# usbmidi_v2.net
KiCad netlist of a schematic drawn in EAGLE
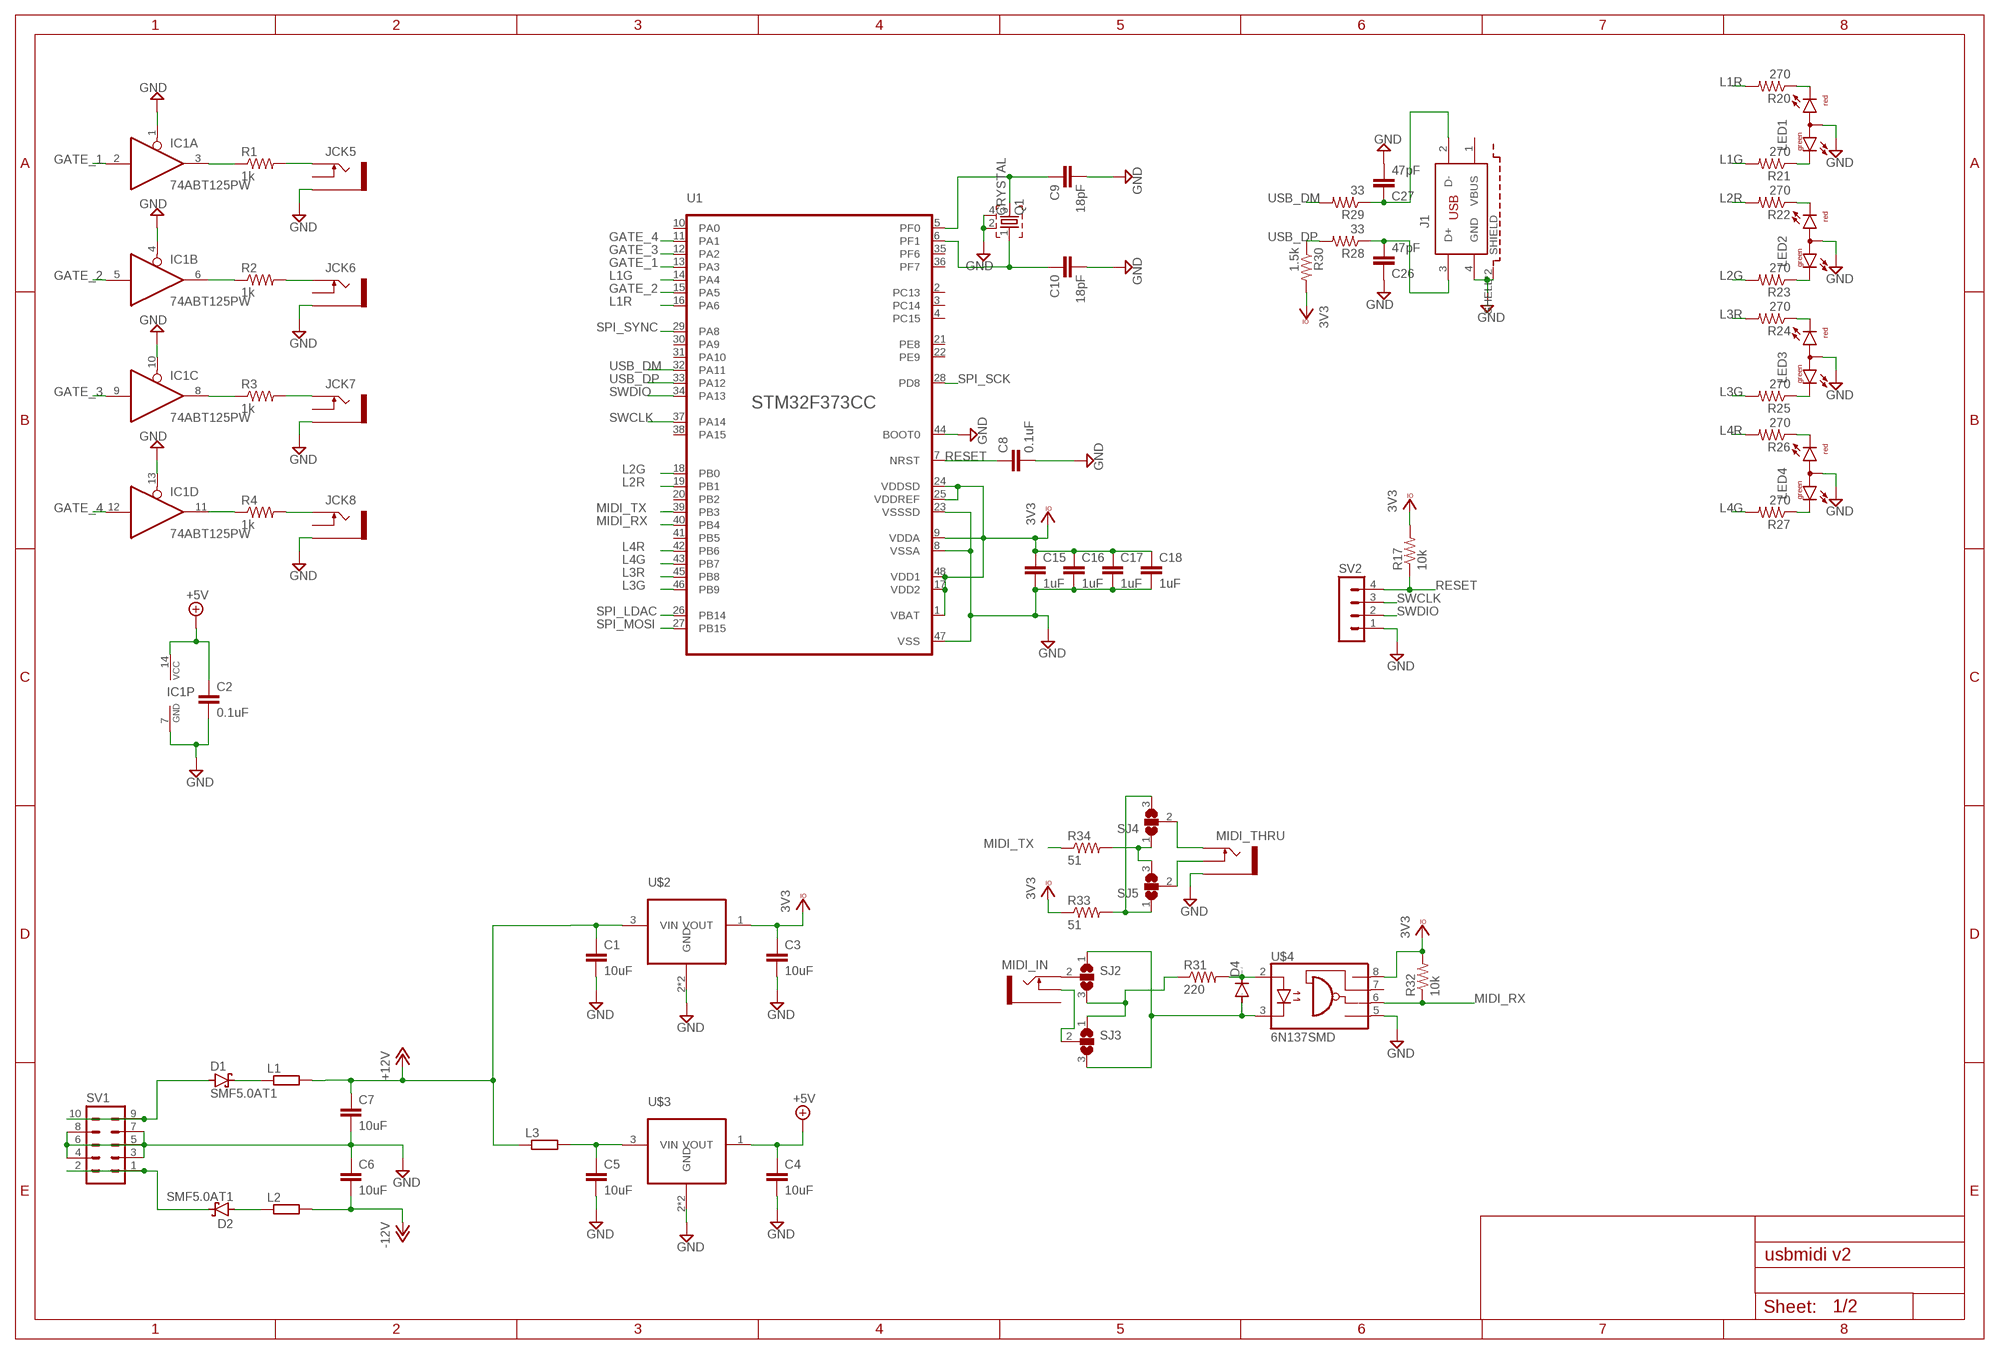
[diagram p0: schematic, sheet 1]
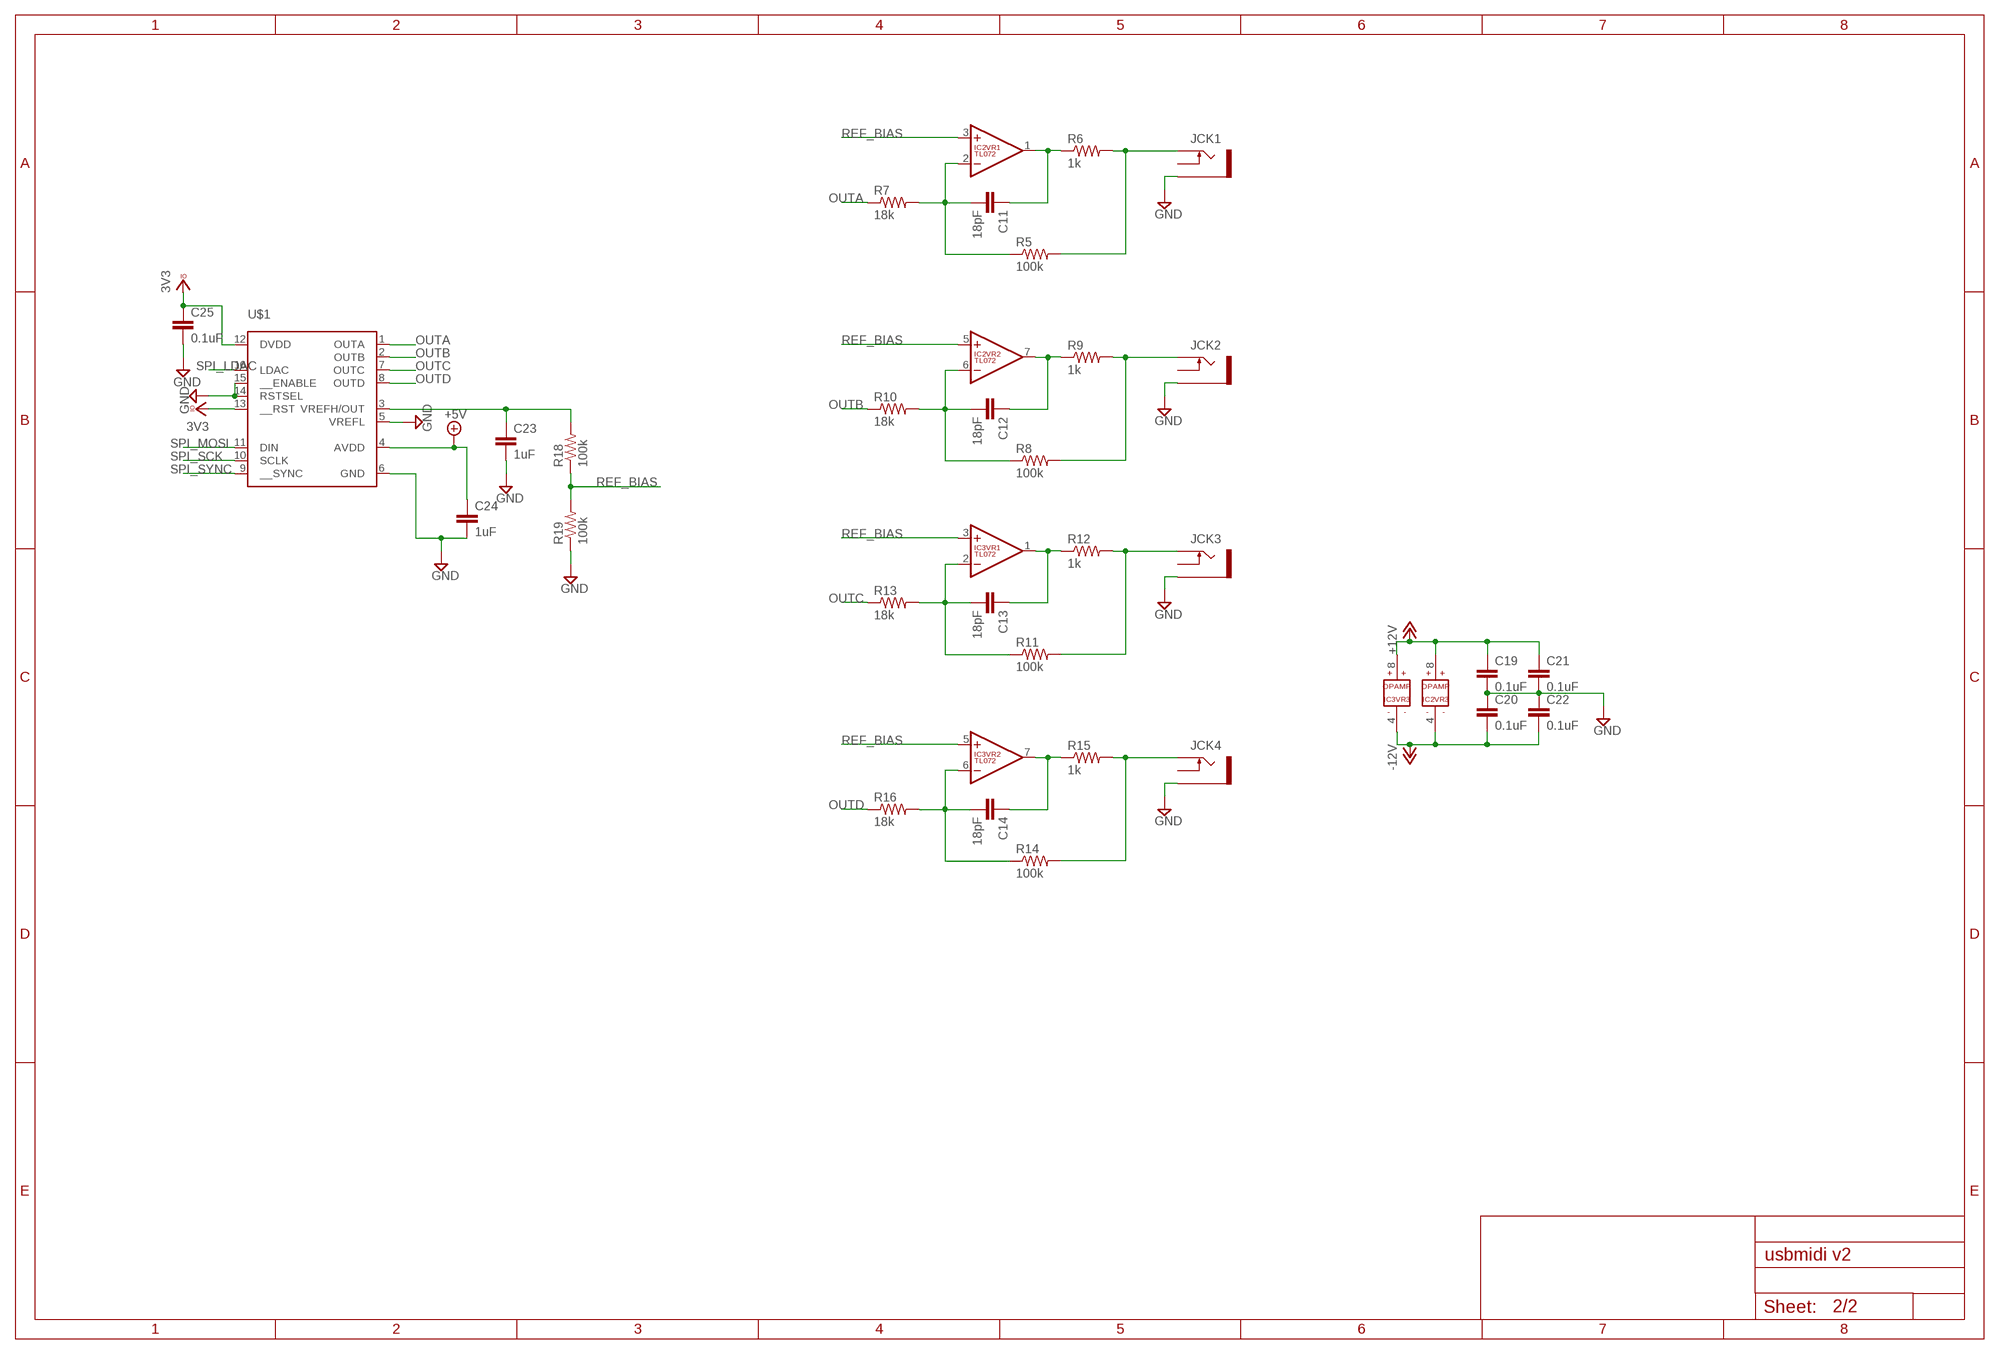
[diagram p1: schematic, sheet 2]

(export (version "E")
  (design (tool "Eeschema 10.0.6"))
  (components
    (comp (ref "C11")
      (value "18pF")
      (footprint "eagle-import:C0603K")
      (libsource (lib "eagle-import") (part "C-EUC0603K"))
    )
    (comp (ref "C12")
      (value "18pF")
      (footprint "eagle-import:C0603K")
      (libsource (lib "eagle-import") (part "C-EUC0603K"))
    )
    (comp (ref "C13")
      (value "18pF")
      (footprint "eagle-import:C0603K")
      (libsource (lib "eagle-import") (part "C-EUC0603K"))
    )
    (comp (ref "C14")
      (value "18pF")
      (footprint "eagle-import:C0603K")
      (libsource (lib "eagle-import") (part "C-EUC0603K"))
    )
    (comp (ref "C19")
      (value "0.1uF")
      (footprint "eagle-import:C0603K")
      (libsource (lib "eagle-import") (part "C-EUC0603K"))
    )
    (comp (ref "C20")
      (value "0.1uF")
      (footprint "eagle-import:C0603K")
      (libsource (lib "eagle-import") (part "C-EUC0603K"))
    )
    (comp (ref "C21")
      (value "0.1uF")
      (footprint "eagle-import:C0603K")
      (libsource (lib "eagle-import") (part "C-EUC0603K"))
    )
    (comp (ref "C22")
      (value "0.1uF")
      (footprint "eagle-import:C0603K")
      (libsource (lib "eagle-import") (part "C-EUC0603K"))
    )
    (comp (ref "C23")
      (value "1uF")
      (footprint "eagle-import:C0603K")
      (libsource (lib "eagle-import") (part "C-EUC0603K"))
    )
    (comp (ref "C24")
      (value "1uF")
      (footprint "eagle-import:C0603K")
      (libsource (lib "eagle-import") (part "C-EUC0603K"))
    )
    (comp (ref "C25")
      (value "0.1uF")
      (footprint "eagle-import:C0603K")
      (libsource (lib "eagle-import") (part "C-EUC0603K"))
    )
    (comp (ref "IC2")
      (value "TL072")
      (footprint "eagle-import:SO08")
      (libsource (lib "eagle-import") (part "TL072"))
    )
    (comp (ref "IC3")
      (value "TL072")
      (footprint "eagle-import:SO08")
      (libsource (lib "eagle-import") (part "TL072"))
    )
    (comp (ref "JCK1")
      (value "THONKICONNNEW")
      (footprint "eagle-import:WQP-PJ301M-12_JACK")
      (libsource (lib "eagle-import") (part "THONKICONNNEW"))
    )
    (comp (ref "JCK2")
      (value "THONKICONNNEW")
      (footprint "eagle-import:WQP-PJ301M-12_JACK")
      (libsource (lib "eagle-import") (part "THONKICONNNEW"))
    )
    (comp (ref "JCK3")
      (value "THONKICONNNEW")
      (footprint "eagle-import:WQP-PJ301M-12_JACK")
      (libsource (lib "eagle-import") (part "THONKICONNNEW"))
    )
    (comp (ref "JCK4")
      (value "THONKICONNNEW")
      (footprint "eagle-import:WQP-PJ301M-12_JACK")
      (libsource (lib "eagle-import") (part "THONKICONNNEW"))
    )
    (comp (ref "R5")
      (value "100k")
      (footprint "eagle-import:R0603")
      (libsource (lib "eagle-import") (part "R-US_R0603"))
    )
    (comp (ref "R6")
      (value "1k")
      (footprint "eagle-import:R0603")
      (libsource (lib "eagle-import") (part "R-US_R0603"))
    )
    (comp (ref "R7")
      (value "18k")
      (footprint "eagle-import:R0603")
      (libsource (lib "eagle-import") (part "R-US_R0603"))
    )
    (comp (ref "R8")
      (value "100k")
      (footprint "eagle-import:R0603")
      (libsource (lib "eagle-import") (part "R-US_R0603"))
    )
    (comp (ref "R9")
      (value "1k")
      (footprint "eagle-import:R0603")
      (libsource (lib "eagle-import") (part "R-US_R0603"))
    )
    (comp (ref "R10")
      (value "18k")
      (footprint "eagle-import:R0603")
      (libsource (lib "eagle-import") (part "R-US_R0603"))
    )
    (comp (ref "R11")
      (value "100k")
      (footprint "eagle-import:R0603")
      (libsource (lib "eagle-import") (part "R-US_R0603"))
    )
    (comp (ref "R12")
      (value "1k")
      (footprint "eagle-import:R0603")
      (libsource (lib "eagle-import") (part "R-US_R0603"))
    )
    (comp (ref "R13")
      (value "18k")
      (footprint "eagle-import:R0603")
      (libsource (lib "eagle-import") (part "R-US_R0603"))
    )
    (comp (ref "R14")
      (value "100k")
      (footprint "eagle-import:R0603")
      (libsource (lib "eagle-import") (part "R-US_R0603"))
    )
    (comp (ref "R15")
      (value "1k")
      (footprint "eagle-import:R0603")
      (libsource (lib "eagle-import") (part "R-US_R0603"))
    )
    (comp (ref "R16")
      (value "18k")
      (footprint "eagle-import:R0603")
      (libsource (lib "eagle-import") (part "R-US_R0603"))
    )
    (comp (ref "R18")
      (value "100k")
      (footprint "eagle-import:R0603")
      (libsource (lib "eagle-import") (part "R-US_R0603"))
    )
    (comp (ref "R19")
      (value "100k")
      (footprint "eagle-import:R0603")
      (libsource (lib "eagle-import") (part "R-US_R0603"))
    )
    (comp (ref "U$1")
      (value "DAC8565")
      (footprint "eagle-import:TSSOP16")
      (libsource (lib "eagle-import") (part "DAC8565"))
    )
    (comp (ref "C1")
      (value "10uF")
      (footprint "eagle-import:C0805")
      (libsource (lib "eagle-import") (part "C-EUC0805"))
    )
    (comp (ref "C2")
      (value "0.1uF")
      (footprint "eagle-import:C0603K")
      (libsource (lib "eagle-import") (part "C-EUC0603K"))
    )
    (comp (ref "C3")
      (value "10uF")
      (footprint "eagle-import:C0805")
      (libsource (lib "eagle-import") (part "C-EUC0805"))
    )
    (comp (ref "C4")
      (value "10uF")
      (footprint "eagle-import:C0805")
      (libsource (lib "eagle-import") (part "C-EUC0805"))
    )
    (comp (ref "C5")
      (value "10uF")
      (footprint "eagle-import:C0805")
      (libsource (lib "eagle-import") (part "C-EUC0805"))
    )
    (comp (ref "C6")
      (value "10uF")
      (footprint "eagle-import:C0805")
      (libsource (lib "eagle-import") (part "C-EUC0805"))
    )
    (comp (ref "C7")
      (value "10uF")
      (footprint "eagle-import:C0805")
      (libsource (lib "eagle-import") (part "C-EUC0805"))
    )
    (comp (ref "C8")
      (value "0.1uF")
      (footprint "eagle-import:C0603K")
      (libsource (lib "eagle-import") (part "C-EUC0603K"))
    )
    (comp (ref "C9")
      (value "18pF")
      (footprint "eagle-import:C0603K")
      (libsource (lib "eagle-import") (part "C-EUC0603K"))
    )
    (comp (ref "C10")
      (value "18pF")
      (footprint "eagle-import:C0603K")
      (libsource (lib "eagle-import") (part "C-EUC0603K"))
    )
    (comp (ref "C15")
      (value "1uF")
      (footprint "eagle-import:C0603K")
      (libsource (lib "eagle-import") (part "C-EUC0603K"))
    )
    (comp (ref "C16")
      (value "1uF")
      (footprint "eagle-import:C0603K")
      (libsource (lib "eagle-import") (part "C-EUC0603K"))
    )
    (comp (ref "C17")
      (value "1uF")
      (footprint "eagle-import:C0603K")
      (libsource (lib "eagle-import") (part "C-EUC0603K"))
    )
    (comp (ref "C18")
      (value "1uF")
      (footprint "eagle-import:C0603K")
      (libsource (lib "eagle-import") (part "C-EUC0603K"))
    )
    (comp (ref "C26")
      (value "47pF")
      (footprint "eagle-import:C0603K")
      (libsource (lib "eagle-import") (part "C-EUC0603K"))
    )
    (comp (ref "C27")
      (value "47pF")
      (footprint "eagle-import:C0603K")
      (libsource (lib "eagle-import") (part "C-EUC0603K"))
    )
    (comp (ref "D1")
      (value "SMF5.0AT1")
      (footprint "eagle-import:SOD123FL")
      (libsource (lib "eagle-import") (part "SMF5.0AT1"))
    )
    (comp (ref "D2")
      (value "SMF5.0AT1")
      (footprint "eagle-import:SOD123FL")
      (libsource (lib "eagle-import") (part "SMF5.0AT1"))
    )
    (comp (ref "D4")
      (value "DIODE-SOD123")
      (footprint "eagle-import:SOD123")
      (libsource (lib "eagle-import") (part "DIODE-SOD123"))
    )
    (comp (ref "IC1")
      (value "74ABT125PW")
      (footprint "eagle-import:TSSOP14")
      (libsource (lib "eagle-import") (part "74125PWABT"))
    )
    (comp (ref "J1")
      (value "61400413321")
      (footprint "eagle-import:61400413321")
      (libsource (lib "eagle-import") (part "61400413321"))
    )
    (comp (ref "JCK5")
      (value "THONKICONNNEW")
      (footprint "eagle-import:WQP-PJ301M-12_JACK")
      (libsource (lib "eagle-import") (part "THONKICONNNEW"))
    )
    (comp (ref "JCK6")
      (value "THONKICONNNEW")
      (footprint "eagle-import:WQP-PJ301M-12_JACK")
      (libsource (lib "eagle-import") (part "THONKICONNNEW"))
    )
    (comp (ref "JCK7")
      (value "THONKICONNNEW")
      (footprint "eagle-import:WQP-PJ301M-12_JACK")
      (libsource (lib "eagle-import") (part "THONKICONNNEW"))
    )
    (comp (ref "JCK8")
      (value "THONKICONNNEW")
      (footprint "eagle-import:WQP-PJ301M-12_JACK")
      (libsource (lib "eagle-import") (part "THONKICONNNEW"))
    )
    (comp (ref "L1")
      (value "R-EU_R0603")
      (footprint "eagle-import:R0603")
      (libsource (lib "eagle-import") (part "R-EU_R0603"))
    )
    (comp (ref "L2")
      (value "R-EU_R0603")
      (footprint "eagle-import:R0603")
      (libsource (lib "eagle-import") (part "R-EU_R0603"))
    )
    (comp (ref "L3")
      (value "R-EU_R0603")
      (footprint "eagle-import:R0603")
      (libsource (lib "eagle-import") (part "R-EU_R0603"))
    )
    (comp (ref "LED1")
      (value "L-115WEGW-CA")
      (footprint "eagle-import:DUOLED-A-3MM")
      (libsource (lib "eagle-import") (part "L-115WEGW-CA"))
    )
    (comp (ref "LED2")
      (value "L-115WEGW-CA")
      (footprint "eagle-import:DUOLED-A-3MM")
      (libsource (lib "eagle-import") (part "L-115WEGW-CA"))
    )
    (comp (ref "LED3")
      (value "L-115WEGW-CA")
      (footprint "eagle-import:DUOLED-A-3MM")
      (libsource (lib "eagle-import") (part "L-115WEGW-CA"))
    )
    (comp (ref "LED4")
      (value "L-115WEGW-CA")
      (footprint "eagle-import:DUOLED-A-3MM")
      (libsource (lib "eagle-import") (part "L-115WEGW-CA"))
    )
    (comp (ref "MIDI_IN")
      (value "THONKICONNNEW")
      (footprint "eagle-import:WQP-PJ301M-12_JACK")
      (libsource (lib "eagle-import") (part "THONKICONNNEW"))
    )
    (comp (ref "MIDI_THRU")
      (value "THONKICONNNEW")
      (footprint "eagle-import:WQP-PJ301M-12_JACK")
      (libsource (lib "eagle-import") (part "THONKICONNNEW"))
    )
    (comp (ref "Q1")
      (value "CRYSTAL")
      (footprint "eagle-import:CTS406")
      (libsource (lib "eagle-import") (part "CRYSTAL"))
    )
    (comp (ref "R1")
      (value "1k")
      (footprint "eagle-import:R0603")
      (libsource (lib "eagle-import") (part "R-US_R0603"))
    )
    (comp (ref "R2")
      (value "1k")
      (footprint "eagle-import:R0603")
      (libsource (lib "eagle-import") (part "R-US_R0603"))
    )
    (comp (ref "R3")
      (value "1k")
      (footprint "eagle-import:R0603")
      (libsource (lib "eagle-import") (part "R-US_R0603"))
    )
    (comp (ref "R4")
      (value "1k")
      (footprint "eagle-import:R0603")
      (libsource (lib "eagle-import") (part "R-US_R0603"))
    )
    (comp (ref "R17")
      (value "10k")
      (footprint "eagle-import:R0603")
      (libsource (lib "eagle-import") (part "R-US_R0603"))
    )
    (comp (ref "R20")
      (value "270")
      (footprint "eagle-import:R0603")
      (libsource (lib "eagle-import") (part "R-US_R0603"))
    )
    (comp (ref "R21")
      (value "270")
      (footprint "eagle-import:R0603")
      (libsource (lib "eagle-import") (part "R-US_R0603"))
    )
    (comp (ref "R22")
      (value "270")
      (footprint "eagle-import:R0603")
      (libsource (lib "eagle-import") (part "R-US_R0603"))
    )
    (comp (ref "R23")
      (value "270")
      (footprint "eagle-import:R0603")
      (libsource (lib "eagle-import") (part "R-US_R0603"))
    )
    (comp (ref "R24")
      (value "270")
      (footprint "eagle-import:R0603")
      (libsource (lib "eagle-import") (part "R-US_R0603"))
    )
    (comp (ref "R25")
      (value "270")
      (footprint "eagle-import:R0603")
      (libsource (lib "eagle-import") (part "R-US_R0603"))
    )
    (comp (ref "R26")
      (value "270")
      (footprint "eagle-import:R0603")
      (libsource (lib "eagle-import") (part "R-US_R0603"))
    )
    (comp (ref "R27")
      (value "270")
      (footprint "eagle-import:R0603")
      (libsource (lib "eagle-import") (part "R-US_R0603"))
    )
    (comp (ref "R28")
      (value "33")
      (footprint "eagle-import:R0603")
      (libsource (lib "eagle-import") (part "R-US_R0603"))
    )
    (comp (ref "R29")
      (value "33")
      (footprint "eagle-import:R0603")
      (libsource (lib "eagle-import") (part "R-US_R0603"))
    )
    (comp (ref "R30")
      (value "1.5k")
      (footprint "eagle-import:R0603")
      (libsource (lib "eagle-import") (part "R-US_R0603"))
    )
    (comp (ref "R31")
      (value "220")
      (footprint "eagle-import:R0603")
      (libsource (lib "eagle-import") (part "R-US_R0603"))
    )
    (comp (ref "R32")
      (value "10k")
      (footprint "eagle-import:R0603")
      (libsource (lib "eagle-import") (part "R-US_R0603"))
    )
    (comp (ref "R33")
      (value "51")
      (footprint "eagle-import:R0603")
      (libsource (lib "eagle-import") (part "R-US_R0603"))
    )
    (comp (ref "R34")
      (value "51")
      (footprint "eagle-import:R0603")
      (libsource (lib "eagle-import") (part "R-US_R0603"))
    )
    (comp (ref "SJ2")
      (value "SJ2W")
      (footprint "eagle-import:SJ_2")
      (libsource (lib "eagle-import") (part "SJ2W"))
    )
    (comp (ref "SJ3")
      (value "SJ2W")
      (footprint "eagle-import:SJ_2")
      (libsource (lib "eagle-import") (part "SJ2W"))
    )
    (comp (ref "SJ4")
      (value "SJ2W")
      (footprint "eagle-import:SJ_2")
      (libsource (lib "eagle-import") (part "SJ2W"))
    )
    (comp (ref "SJ5")
      (value "SJ2W")
      (footprint "eagle-import:SJ_2")
      (libsource (lib "eagle-import") (part "SJ2W"))
    )
    (comp (ref "SV1")
      (value "MA05-2")
      (footprint "eagle-import:MA05-2")
      (libsource (lib "eagle-import") (part "MA05-2"))
    )
    (comp (ref "SV2")
      (value "MA04-1")
      (footprint "eagle-import:MA04-1")
      (libsource (lib "eagle-import") (part "MA04-1"))
    )
    (comp (ref "U$2")
      (value "LD2981ABUSOT89")
      (footprint "eagle-import:SOT89")
      (libsource (lib "eagle-import") (part "LD2981ABUSOT89"))
    )
    (comp (ref "U$3")
      (value "LD2981ABUSOT89")
      (footprint "eagle-import:SOT89")
      (libsource (lib "eagle-import") (part "LD2981ABUSOT89"))
    )
    (comp (ref "U$4")
      (value "6N137SMD")
      (footprint "eagle-import:DIL8-SMD")
      (libsource (lib "eagle-import") (part "6N137SMD"))
    )
    (comp (ref "U1")
      (value "STM32F373LQFP48")
      (footprint "eagle-import:LQFP48")
      (libsource (lib "eagle-import") (part "STM32F373LQFP48"))
    )
  )
  (nets
    (net (code "1") (name "+5V") (class "Default")
      (node (ref "C2") (pin "1") (pinfunction "1_1") (pintype "passive"))
      (node (ref "C24") (pin "1") (pinfunction "1_1") (pintype "passive"))
      (node (ref "C4") (pin "1") (pinfunction "1_1") (pintype "passive"))
      (node (ref "IC1") (pin "14") (pinfunction "VCC_14") (pintype "power_in"))
      (node (ref "U$1") (pin "4") (pinfunction "AVDD_4") (pintype "bidirectional"))
      (node (ref "U$3") (pin "1") (pinfunction "VOUT_1") (pintype "bidirectional"))
    )
    (net (code "2") (name "+12V") (class "Default")
      (node (ref "C1") (pin "1") (pinfunction "1_1") (pintype "passive"))
      (node (ref "C19") (pin "1") (pinfunction "1_1") (pintype "passive"))
      (node (ref "C21") (pin "1") (pinfunction "1_1") (pintype "passive"))
      (node (ref "C7") (pin "1") (pinfunction "1_1") (pintype "passive"))
      (node (ref "IC2") (pin "8") (pinfunction "V+_8") (pintype "power_in"))
      (node (ref "IC3") (pin "8") (pinfunction "V+_8") (pintype "power_in"))
      (node (ref "L1") (pin "2") (pinfunction "2_2") (pintype "passive"))
      (node (ref "L3") (pin "1") (pinfunction "1_1") (pintype "passive"))
      (node (ref "U$2") (pin "3") (pinfunction "VIN_3") (pintype "bidirectional"))
    )
    (net (code "3") (name "-12V") (class "Default")
      (node (ref "C20") (pin "2") (pinfunction "2_2") (pintype "passive"))
      (node (ref "C22") (pin "2") (pinfunction "2_2") (pintype "passive"))
      (node (ref "C6") (pin "2") (pinfunction "2_2") (pintype "passive"))
      (node (ref "IC2") (pin "4") (pinfunction "V-_4") (pintype "power_in"))
      (node (ref "IC3") (pin "4") (pinfunction "V-_4") (pintype "power_in"))
      (node (ref "L2") (pin "2") (pinfunction "2_2") (pintype "passive"))
    )
    (net (code "4") (name "GATE_1") (class "Default")
      (node (ref "IC1") (pin "2") (pinfunction "I_2") (pintype "input"))
      (node (ref "U1") (pin "13") (pinfunction "PA3_13") (pintype "bidirectional"))
    )
    (net (code "5") (name "GATE_2") (class "Default")
      (node (ref "IC1") (pin "5") (pinfunction "I_5") (pintype "input"))
      (node (ref "U1") (pin "15") (pinfunction "PA5_15") (pintype "bidirectional"))
    )
    (net (code "6") (name "GATE_3") (class "Default")
      (node (ref "IC1") (pin "9") (pinfunction "I_9") (pintype "input"))
      (node (ref "U1") (pin "12") (pinfunction "PA2_12") (pintype "bidirectional"))
    )
    (net (code "7") (name "GATE_4") (class "Default")
      (node (ref "IC1") (pin "12") (pinfunction "I_12") (pintype "input"))
      (node (ref "U1") (pin "11") (pinfunction "PA1_11") (pintype "bidirectional"))
    )
    (net (code "8") (name "GND") (class "Default")
      (node (ref "C1") (pin "2") (pinfunction "2_2") (pintype "passive"))
      (node (ref "C10") (pin "2") (pinfunction "2_2") (pintype "passive"))
      (node (ref "C15") (pin "2") (pinfunction "2_2") (pintype "passive"))
      (node (ref "C16") (pin "2") (pinfunction "2_2") (pintype "passive"))
      (node (ref "C17") (pin "2") (pinfunction "2_2") (pintype "passive"))
      (node (ref "C18") (pin "2") (pinfunction "2_2") (pintype "passive"))
      (node (ref "C19") (pin "2") (pinfunction "2_2") (pintype "passive"))
      (node (ref "C2") (pin "2") (pinfunction "2_2") (pintype "passive"))
      (node (ref "C20") (pin "1") (pinfunction "1_1") (pintype "passive"))
      (node (ref "C21") (pin "2") (pinfunction "2_2") (pintype "passive"))
      (node (ref "C22") (pin "1") (pinfunction "1_1") (pintype "passive"))
      (node (ref "C23") (pin "2") (pinfunction "2_2") (pintype "passive"))
      (node (ref "C24") (pin "2") (pinfunction "2_2") (pintype "passive"))
      (node (ref "C25") (pin "2") (pinfunction "2_2") (pintype "passive"))
      (node (ref "C26") (pin "1") (pinfunction "1_1") (pintype "passive"))
      (node (ref "C27") (pin "2") (pinfunction "2_2") (pintype "passive"))
      (node (ref "C3") (pin "2") (pinfunction "2_2") (pintype "passive"))
      (node (ref "C4") (pin "2") (pinfunction "2_2") (pintype "passive"))
      (node (ref "C5") (pin "2") (pinfunction "2_2") (pintype "passive"))
      (node (ref "C6") (pin "1") (pinfunction "1_1") (pintype "passive"))
      (node (ref "C7") (pin "2") (pinfunction "2_2") (pintype "passive"))
      (node (ref "C8") (pin "2") (pinfunction "2_2") (pintype "passive"))
      (node (ref "C9") (pin "2") (pinfunction "2_2") (pintype "passive"))
      (node (ref "IC1") (pin "1") (pinfunction "OE_1") (pintype "input"))
      (node (ref "IC1") (pin "10") (pinfunction "OE_10") (pintype "input"))
      (node (ref "IC1") (pin "13") (pinfunction "OE_13") (pintype "input"))
      (node (ref "IC1") (pin "4") (pinfunction "OE_4") (pintype "input"))
      (node (ref "IC1") (pin "7") (pinfunction "GND_7") (pintype "power_in"))
      (node (ref "J1") (pin "4") (pinfunction "GND_4") (pintype "bidirectional"))
      (node (ref "J1") (pin "SHELL") (pinfunction "SHIELD_SHELL") (pintype "bidirectional"))
      (node (ref "J1") (pin "SHELL1") (pinfunction "SHIELD_SHELL1") (pintype "bidirectional"))
      (node (ref "JCK1") (pin "P$3_SLEEVE") (pinfunction "SLEEVE_P$3_SLEEVE") (pintype "passive"))
      (node (ref "JCK2") (pin "P$3_SLEEVE") (pinfunction "SLEEVE_P$3_SLEEVE") (pintype "passive"))
      (node (ref "JCK3") (pin "P$3_SLEEVE") (pinfunction "SLEEVE_P$3_SLEEVE") (pintype "passive"))
      (node (ref "JCK4") (pin "P$3_SLEEVE") (pinfunction "SLEEVE_P$3_SLEEVE") (pintype "passive"))
      (node (ref "JCK5") (pin "P$3_SLEEVE") (pinfunction "SLEEVE_P$3_SLEEVE") (pintype "passive"))
      (node (ref "JCK6") (pin "P$3_SLEEVE") (pinfunction "SLEEVE_P$3_SLEEVE") (pintype "passive"))
      (node (ref "JCK7") (pin "P$3_SLEEVE") (pinfunction "SLEEVE_P$3_SLEEVE") (pintype "passive"))
      (node (ref "JCK8") (pin "P$3_SLEEVE") (pinfunction "SLEEVE_P$3_SLEEVE") (pintype "passive"))
      (node (ref "LED1") (pin "2") (pinfunction "A_2") (pintype "passive"))
      (node (ref "LED2") (pin "2") (pinfunction "A_2") (pintype "passive"))
      (node (ref "LED3") (pin "2") (pinfunction "A_2") (pintype "passive"))
      (node (ref "LED4") (pin "2") (pinfunction "A_2") (pintype "passive"))
      (node (ref "MIDI_THRU") (pin "P$3_SLEEVE") (pinfunction "SLEEVE_P$3_SLEEVE") (pintype "passive"))
      (node (ref "Q1") (pin "2") (pinfunction "2_2") (pintype "passive"))
      (node (ref "Q1") (pin "4") (pinfunction "4_4") (pintype "passive"))
      (node (ref "R19") (pin "1") (pinfunction "1_1") (pintype "passive"))
      (node (ref "SV1") (pin "3") (pinfunction "3_3") (pintype "passive"))
      (node (ref "SV1") (pin "4") (pinfunction "4_4") (pintype "passive"))
      (node (ref "SV1") (pin "5") (pinfunction "5_5") (pintype "passive"))
      (node (ref "SV1") (pin "6") (pinfunction "6_6") (pintype "passive"))
      (node (ref "SV1") (pin "7") (pinfunction "7_7") (pintype "passive"))
      (node (ref "SV1") (pin "8") (pinfunction "8_8") (pintype "passive"))
      (node (ref "SV2") (pin "1") (pinfunction "1_1") (pintype "passive"))
      (node (ref "U$1") (pin "14") (pinfunction "RSTSEL_14") (pintype "bidirectional"))
      (node (ref "U$1") (pin "15") (pinfunction "__ENABLE_15") (pintype "bidirectional"))
      (node (ref "U$1") (pin "5") (pinfunction "VREFL_5") (pintype "bidirectional"))
      (node (ref "U$1") (pin "6") (pinfunction "GND_6") (pintype "bidirectional"))
      (node (ref "U$2") (pin "2") (pinfunction "GND_2") (pintype "bidirectional"))
      (node (ref "U$2") (pin "2@1") (pinfunction "GND_2@1") (pintype "bidirectional"))
      (node (ref "U$3") (pin "2") (pinfunction "GND_2") (pintype "bidirectional"))
      (node (ref "U$3") (pin "2@1") (pinfunction "GND_2@1") (pintype "bidirectional"))
      (node (ref "U$4") (pin "5") (pinfunction "GND_5") (pintype "passive"))
      (node (ref "U1") (pin "23") (pinfunction "VSSSD_23") (pintype "bidirectional"))
      (node (ref "U1") (pin "44") (pinfunction "BOOT0_44") (pintype "bidirectional"))
      (node (ref "U1") (pin "47") (pinfunction "VSS_47") (pintype "bidirectional"))
      (node (ref "U1") (pin "8") (pinfunction "VSSA_8") (pintype "bidirectional"))
    )
    (net (code "9") (name "L1G") (class "Default")
      (node (ref "R21") (pin "2") (pinfunction "2_2") (pintype "passive"))
      (node (ref "U1") (pin "14") (pinfunction "PA4_14") (pintype "bidirectional"))
    )
    (net (code "10") (name "L1R") (class "Default")
      (node (ref "R20") (pin "2") (pinfunction "2_2") (pintype "passive"))
      (node (ref "U1") (pin "16") (pinfunction "PA6_16") (pintype "bidirectional"))
    )
    (net (code "11") (name "L2G") (class "Default")
      (node (ref "R23") (pin "2") (pinfunction "2_2") (pintype "passive"))
      (node (ref "U1") (pin "18") (pinfunction "PB0_18") (pintype "bidirectional"))
    )
    (net (code "12") (name "L2R") (class "Default")
      (node (ref "R22") (pin "2") (pinfunction "2_2") (pintype "passive"))
      (node (ref "U1") (pin "19") (pinfunction "PB1_19") (pintype "bidirectional"))
    )
    (net (code "13") (name "L3G") (class "Default")
      (node (ref "R25") (pin "2") (pinfunction "2_2") (pintype "passive"))
      (node (ref "U1") (pin "46") (pinfunction "PB9_46") (pintype "bidirectional"))
    )
    (net (code "14") (name "L3R") (class "Default")
      (node (ref "R24") (pin "2") (pinfunction "2_2") (pintype "passive"))
      (node (ref "U1") (pin "45") (pinfunction "PB8_45") (pintype "bidirectional"))
    )
    (net (code "15") (name "L4G") (class "Default")
      (node (ref "R27") (pin "2") (pinfunction "2_2") (pintype "passive"))
      (node (ref "U1") (pin "43") (pinfunction "PB7_43") (pintype "bidirectional"))
    )
    (net (code "16") (name "L4R") (class "Default")
      (node (ref "R26") (pin "2") (pinfunction "2_2") (pintype "passive"))
      (node (ref "U1") (pin "42") (pinfunction "PB6_42") (pintype "bidirectional"))
    )
    (net (code "17") (name "MIDI_RX") (class "Default")
      (node (ref "R32") (pin "1") (pinfunction "1_1") (pintype "passive"))
      (node (ref "U$4") (pin "6") (pinfunction "VO_6") (pintype "passive"))
      (node (ref "U1") (pin "40") (pinfunction "PB4_40") (pintype "bidirectional"))
    )
    (net (code "18") (name "MIDI_TX") (class "Default")
      (node (ref "R34") (pin "1") (pinfunction "1_1") (pintype "passive"))
      (node (ref "U1") (pin "39") (pinfunction "PB3_39") (pintype "bidirectional"))
    )
    (net (code "19") (name "Net-(D1-PadA)") (class "Default")
      (node (ref "D1") (pin "A") (pinfunction "A_A") (pintype "passive"))
      (node (ref "SV1") (pin "10") (pinfunction "10_10") (pintype "passive"))
      (node (ref "SV1") (pin "9") (pinfunction "9_9") (pintype "passive"))
    )
    (net (code "20") (name "Net-(D1-PadC)") (class "Default")
      (node (ref "D1") (pin "C") (pinfunction "C_C") (pintype "passive"))
      (node (ref "L1") (pin "1") (pinfunction "1_1") (pintype "passive"))
    )
    (net (code "21") (name "Net-(D2-PadA)") (class "Default")
      (node (ref "D2") (pin "A") (pinfunction "A_A") (pintype "passive"))
      (node (ref "L2") (pin "1") (pinfunction "1_1") (pintype "passive"))
    )
    (net (code "22") (name "Net-(D2-PadC)") (class "Default")
      (node (ref "D2") (pin "C") (pinfunction "C_C") (pintype "passive"))
      (node (ref "SV1") (pin "1") (pinfunction "1_1") (pintype "passive"))
      (node (ref "SV1") (pin "2") (pinfunction "2_2") (pintype "passive"))
    )
    (net (code "23") (name "Net-(IC1A-O)") (class "Default")
      (node (ref "IC1") (pin "3") (pinfunction "O_3") (pintype "tri_state"))
      (node (ref "R1") (pin "1") (pinfunction "1_1") (pintype "passive"))
    )
    (net (code "24") (name "Net-(IC1B-O)") (class "Default")
      (node (ref "IC1") (pin "6") (pinfunction "O_6") (pintype "tri_state"))
      (node (ref "R2") (pin "1") (pinfunction "1_1") (pintype "passive"))
    )
    (net (code "25") (name "Net-(IC1C-O)") (class "Default")
      (node (ref "IC1") (pin "8") (pinfunction "O_8") (pintype "tri_state"))
      (node (ref "R3") (pin "1") (pinfunction "1_1") (pintype "passive"))
    )
    (net (code "26") (name "Net-(IC1D-O)") (class "Default")
      (node (ref "IC1") (pin "11") (pinfunction "O_11") (pintype "tri_state"))
      (node (ref "R4") (pin "1") (pinfunction "1_1") (pintype "passive"))
    )
    (net (code "27") (name "Net-(IC2A--IN)") (class "Default")
      (node (ref "C11") (pin "2") (pinfunction "2_2") (pintype "passive"))
      (node (ref "IC2") (pin "2") (pinfunction "-IN_2") (pintype "input"))
      (node (ref "R5") (pin "1") (pinfunction "1_1") (pintype "passive"))
      (node (ref "R7") (pin "2") (pinfunction "2_2") (pintype "passive"))
    )
    (net (code "28") (name "Net-(IC2A-OUT)") (class "Default")
      (node (ref "C11") (pin "1") (pinfunction "1_1") (pintype "passive"))
      (node (ref "IC2") (pin "1") (pinfunction "OUT_1") (pintype "output"))
      (node (ref "R6") (pin "1") (pinfunction "1_1") (pintype "passive"))
    )
    (net (code "29") (name "Net-(IC2B--IN)") (class "Default")
      (node (ref "C12") (pin "2") (pinfunction "2_2") (pintype "passive"))
      (node (ref "IC2") (pin "6") (pinfunction "-IN_6") (pintype "input"))
      (node (ref "R10") (pin "2") (pinfunction "2_2") (pintype "passive"))
      (node (ref "R8") (pin "1") (pinfunction "1_1") (pintype "passive"))
    )
    (net (code "30") (name "Net-(IC2B-OUT)") (class "Default")
      (node (ref "C12") (pin "1") (pinfunction "1_1") (pintype "passive"))
      (node (ref "IC2") (pin "7") (pinfunction "OUT_7") (pintype "output"))
      (node (ref "R9") (pin "1") (pinfunction "1_1") (pintype "passive"))
    )
    (net (code "31") (name "Net-(IC3A--IN)") (class "Default")
      (node (ref "C13") (pin "2") (pinfunction "2_2") (pintype "passive"))
      (node (ref "IC3") (pin "2") (pinfunction "-IN_2") (pintype "input"))
      (node (ref "R11") (pin "1") (pinfunction "1_1") (pintype "passive"))
      (node (ref "R13") (pin "2") (pinfunction "2_2") (pintype "passive"))
    )
    (net (code "32") (name "Net-(IC3A-OUT)") (class "Default")
      (node (ref "C13") (pin "1") (pinfunction "1_1") (pintype "passive"))
      (node (ref "IC3") (pin "1") (pinfunction "OUT_1") (pintype "output"))
      (node (ref "R12") (pin "1") (pinfunction "1_1") (pintype "passive"))
    )
    (net (code "33") (name "Net-(IC3B--IN)") (class "Default")
      (node (ref "C14") (pin "2") (pinfunction "2_2") (pintype "passive"))
      (node (ref "IC3") (pin "6") (pinfunction "-IN_6") (pintype "input"))
      (node (ref "R14") (pin "1") (pinfunction "1_1") (pintype "passive"))
      (node (ref "R16") (pin "2") (pinfunction "2_2") (pintype "passive"))
    )
    (net (code "34") (name "Net-(IC3B-OUT)") (class "Default")
      (node (ref "C14") (pin "1") (pinfunction "1_1") (pintype "passive"))
      (node (ref "IC3") (pin "7") (pinfunction "OUT_7") (pintype "output"))
      (node (ref "R15") (pin "1") (pinfunction "1_1") (pintype "passive"))
    )
    (net (code "35") (name "Net-(J1-D+)") (class "Default")
      (node (ref "C26") (pin "2") (pinfunction "2_2") (pintype "passive"))
      (node (ref "J1") (pin "3") (pinfunction "D+_3") (pintype "bidirectional"))
      (node (ref "R28") (pin "1") (pinfunction "1_1") (pintype "passive"))
    )
    (net (code "36") (name "Net-(J1-D-)") (class "Default")
      (node (ref "C27") (pin "1") (pinfunction "1_1") (pintype "passive"))
      (node (ref "J1") (pin "2") (pinfunction "D-_2") (pintype "bidirectional"))
      (node (ref "R29") (pin "1") (pinfunction "1_1") (pintype "passive"))
    )
    (net (code "37") (name "Net-(JCK1-TIP)") (class "Default")
      (node (ref "JCK1") (pin "P$1_TIP") (pinfunction "TIP_P$1_TIP") (pintype "passive"))
      (node (ref "R5") (pin "2") (pinfunction "2_2") (pintype "passive"))
      (node (ref "R6") (pin "2") (pinfunction "2_2") (pintype "passive"))
    )
    (net (code "38") (name "Net-(JCK2-TIP)") (class "Default")
      (node (ref "JCK2") (pin "P$1_TIP") (pinfunction "TIP_P$1_TIP") (pintype "passive"))
      (node (ref "R8") (pin "2") (pinfunction "2_2") (pintype "passive"))
      (node (ref "R9") (pin "2") (pinfunction "2_2") (pintype "passive"))
    )
    (net (code "39") (name "Net-(JCK3-TIP)") (class "Default")
      (node (ref "JCK3") (pin "P$1_TIP") (pinfunction "TIP_P$1_TIP") (pintype "passive"))
      (node (ref "R11") (pin "2") (pinfunction "2_2") (pintype "passive"))
      (node (ref "R12") (pin "2") (pinfunction "2_2") (pintype "passive"))
    )
    (net (code "40") (name "Net-(JCK4-TIP)") (class "Default")
      (node (ref "JCK4") (pin "P$1_TIP") (pinfunction "TIP_P$1_TIP") (pintype "passive"))
      (node (ref "R14") (pin "2") (pinfunction "2_2") (pintype "passive"))
      (node (ref "R15") (pin "2") (pinfunction "2_2") (pintype "passive"))
    )
    (net (code "41") (name "Net-(JCK5-TIP)") (class "Default")
      (node (ref "JCK5") (pin "P$1_TIP") (pinfunction "TIP_P$1_TIP") (pintype "passive"))
      (node (ref "R1") (pin "2") (pinfunction "2_2") (pintype "passive"))
    )
    (net (code "42") (name "Net-(JCK6-TIP)") (class "Default")
      (node (ref "JCK6") (pin "P$1_TIP") (pinfunction "TIP_P$1_TIP") (pintype "passive"))
      (node (ref "R2") (pin "2") (pinfunction "2_2") (pintype "passive"))
    )
    (net (code "43") (name "Net-(JCK7-TIP)") (class "Default")
      (node (ref "JCK7") (pin "P$1_TIP") (pinfunction "TIP_P$1_TIP") (pintype "passive"))
      (node (ref "R3") (pin "2") (pinfunction "2_2") (pintype "passive"))
    )
    (net (code "44") (name "Net-(JCK8-TIP)") (class "Default")
      (node (ref "JCK8") (pin "P$1_TIP") (pinfunction "TIP_P$1_TIP") (pintype "passive"))
      (node (ref "R4") (pin "2") (pinfunction "2_2") (pintype "passive"))
    )
    (net (code "45") (name "Net-(LED1-CG)") (class "Default")
      (node (ref "LED1") (pin "1") (pinfunction "CG_1") (pintype "passive"))
      (node (ref "R21") (pin "1") (pinfunction "1_1") (pintype "passive"))
    )
    (net (code "46") (name "Net-(LED1-CR)") (class "Default")
      (node (ref "LED1") (pin "3") (pinfunction "CR_3") (pintype "passive"))
      (node (ref "R20") (pin "1") (pinfunction "1_1") (pintype "passive"))
    )
    (net (code "47") (name "Net-(LED2-CG)") (class "Default")
      (node (ref "LED2") (pin "1") (pinfunction "CG_1") (pintype "passive"))
      (node (ref "R23") (pin "1") (pinfunction "1_1") (pintype "passive"))
    )
    (net (code "48") (name "Net-(LED2-CR)") (class "Default")
      (node (ref "LED2") (pin "3") (pinfunction "CR_3") (pintype "passive"))
      (node (ref "R22") (pin "1") (pinfunction "1_1") (pintype "passive"))
    )
    (net (code "49") (name "Net-(LED3-CG)") (class "Default")
      (node (ref "LED3") (pin "1") (pinfunction "CG_1") (pintype "passive"))
      (node (ref "R25") (pin "1") (pinfunction "1_1") (pintype "passive"))
    )
    (net (code "50") (name "Net-(LED3-CR)") (class "Default")
      (node (ref "LED3") (pin "3") (pinfunction "CR_3") (pintype "passive"))
      (node (ref "R24") (pin "1") (pinfunction "1_1") (pintype "passive"))
    )
    (net (code "51") (name "Net-(LED4-CG)") (class "Default")
      (node (ref "LED4") (pin "1") (pinfunction "CG_1") (pintype "passive"))
      (node (ref "R27") (pin "1") (pinfunction "1_1") (pintype "passive"))
    )
    (net (code "52") (name "Net-(LED4-CR)") (class "Default")
      (node (ref "LED4") (pin "3") (pinfunction "CR_3") (pintype "passive"))
      (node (ref "R26") (pin "1") (pinfunction "1_1") (pintype "passive"))
    )
    (net (code "53") (name "Net-(MIDI_IN-SWITCH)") (class "Default")
      (node (ref "MIDI_IN") (pin "P$2_SWITCH") (pinfunction "SWITCH_P$2_SWITCH") (pintype "passive"))
      (node (ref "SJ3") (pin "2") (pinfunction "2_2") (pintype "passive"))
    )
    (net (code "54") (name "Net-(MIDI_IN-TIP)") (class "Default")
      (node (ref "MIDI_IN") (pin "P$1_TIP") (pinfunction "TIP_P$1_TIP") (pintype "passive"))
      (node (ref "SJ2") (pin "2") (pinfunction "2_2") (pintype "passive"))
    )
    (net (code "55") (name "Net-(MIDI_THRU-SWITCH)") (class "Default")
      (node (ref "MIDI_THRU") (pin "P$2_SWITCH") (pinfunction "SWITCH_P$2_SWITCH") (pintype "passive"))
      (node (ref "SJ5") (pin "2") (pinfunction "2_2") (pintype "passive"))
    )
    (net (code "56") (name "Net-(MIDI_THRU-TIP)") (class "Default")
      (node (ref "MIDI_THRU") (pin "P$1_TIP") (pinfunction "TIP_P$1_TIP") (pintype "passive"))
      (node (ref "SJ4") (pin "2") (pinfunction "2_2") (pintype "passive"))
    )
    (net (code "57") (name "Net-(R31-Pad1)") (class "Default")
      (node (ref "R31") (pin "1") (pinfunction "1_1") (pintype "passive"))
      (node (ref "SJ2") (pin "3") (pinfunction "3_3") (pintype "passive"))
      (node (ref "SJ3") (pin "1") (pinfunction "1_1") (pintype "passive"))
    )
    (net (code "58") (name "Net-(R33-Pad2)") (class "Default")
      (node (ref "R33") (pin "2") (pinfunction "2_2") (pintype "passive"))
      (node (ref "SJ4") (pin "3") (pinfunction "3_3") (pintype "passive"))
      (node (ref "SJ5") (pin "1") (pinfunction "1_1") (pintype "passive"))
    )
    (net (code "59") (name "Net-(R34-Pad2)") (class "Default")
      (node (ref "R34") (pin "2") (pinfunction "2_2") (pintype "passive"))
      (node (ref "SJ4") (pin "1") (pinfunction "1_1") (pintype "passive"))
      (node (ref "SJ5") (pin "3") (pinfunction "3_3") (pintype "passive"))
    )
    (net (code "60") (name "Net-(U$1-VREFH{slash}OUT)") (class "Default")
      (node (ref "C23") (pin "1") (pinfunction "1_1") (pintype "passive"))
      (node (ref "R18") (pin "2") (pinfunction "2_2") (pintype "passive"))
      (node (ref "U$1") (pin "3") (pinfunction "VREFH/OUT_3") (pintype "bidirectional"))
    )
    (net (code "61") (name "Net-(U$3-VIN)") (class "Default")
      (node (ref "C5") (pin "1") (pinfunction "1_1") (pintype "passive"))
      (node (ref "L3") (pin "2") (pinfunction "2_2") (pintype "passive"))
      (node (ref "U$3") (pin "3") (pinfunction "VIN_3") (pintype "bidirectional"))
    )
    (net (code "62") (name "Net-(U$4-A)") (class "Default")
      (node (ref "D4") (pin "C") (pinfunction "C_C") (pintype "passive"))
      (node (ref "R31") (pin "2") (pinfunction "2_2") (pintype "passive"))
      (node (ref "U$4") (pin "2") (pinfunction "A_2") (pintype "passive"))
    )
    (net (code "63") (name "Net-(U$4-C)") (class "Default")
      (node (ref "D4") (pin "A") (pinfunction "A_A") (pintype "passive"))
      (node (ref "SJ2") (pin "1") (pinfunction "1_1") (pintype "passive"))
      (node (ref "SJ3") (pin "3") (pinfunction "3_3") (pintype "passive"))
      (node (ref "U$4") (pin "3") (pinfunction "C_3") (pintype "passive"))
    )
    (net (code "64") (name "Net-(U1-PF0)") (class "Default")
      (node (ref "C9") (pin "1") (pinfunction "1_1") (pintype "passive"))
      (node (ref "Q1") (pin "3") (pinfunction "3_3") (pintype "passive"))
      (node (ref "U1") (pin "5") (pinfunction "PF0_5") (pintype "bidirectional"))
    )
    (net (code "65") (name "Net-(U1-PF1)") (class "Default")
      (node (ref "C10") (pin "1") (pinfunction "1_1") (pintype "passive"))
      (node (ref "Q1") (pin "1") (pinfunction "1_1") (pintype "passive"))
      (node (ref "U1") (pin "6") (pinfunction "PF1_6") (pintype "bidirectional"))
    )
    (net (code "66") (name "OUTA") (class "Default")
      (node (ref "R7") (pin "1") (pinfunction "1_1") (pintype "passive"))
      (node (ref "U$1") (pin "1") (pinfunction "OUTA_1") (pintype "bidirectional"))
    )
    (net (code "67") (name "OUTB") (class "Default")
      (node (ref "R10") (pin "1") (pinfunction "1_1") (pintype "passive"))
      (node (ref "U$1") (pin "2") (pinfunction "OUTB_2") (pintype "bidirectional"))
    )
    (net (code "68") (name "OUTC") (class "Default")
      (node (ref "R13") (pin "1") (pinfunction "1_1") (pintype "passive"))
      (node (ref "U$1") (pin "7") (pinfunction "OUTC_7") (pintype "bidirectional"))
    )
    (net (code "69") (name "OUTD") (class "Default")
      (node (ref "R16") (pin "1") (pinfunction "1_1") (pintype "passive"))
      (node (ref "U$1") (pin "8") (pinfunction "OUTD_8") (pintype "bidirectional"))
    )
    (net (code "70") (name "REF_BIAS") (class "Default")
      (node (ref "IC2") (pin "3") (pinfunction "+IN_3") (pintype "input"))
      (node (ref "IC2") (pin "5") (pinfunction "+IN_5") (pintype "input"))
      (node (ref "IC3") (pin "3") (pinfunction "+IN_3") (pintype "input"))
      (node (ref "IC3") (pin "5") (pinfunction "+IN_5") (pintype "input"))
      (node (ref "R18") (pin "1") (pinfunction "1_1") (pintype "passive"))
      (node (ref "R19") (pin "2") (pinfunction "2_2") (pintype "passive"))
    )
    (net (code "71") (name "RESET") (class "Default")
      (node (ref "C8") (pin "1") (pinfunction "1_1") (pintype "passive"))
      (node (ref "R17") (pin "1") (pinfunction "1_1") (pintype "passive"))
      (node (ref "SV2") (pin "4") (pinfunction "4_4") (pintype "passive"))
      (node (ref "U1") (pin "7") (pinfunction "NRST_7") (pintype "bidirectional"))
    )
    (net (code "72") (name "SPI_LDAC") (class "Default")
      (node (ref "U$1") (pin "16") (pinfunction "LDAC_16") (pintype "bidirectional"))
      (node (ref "U1") (pin "26") (pinfunction "PB14_26") (pintype "bidirectional"))
    )
    (net (code "73") (name "SPI_MOSI") (class "Default")
      (node (ref "U$1") (pin "11") (pinfunction "DIN_11") (pintype "bidirectional"))
      (node (ref "U1") (pin "27") (pinfunction "PB15_27") (pintype "bidirectional"))
    )
    (net (code "74") (name "SPI_SCK") (class "Default")
      (node (ref "U$1") (pin "10") (pinfunction "SCLK_10") (pintype "bidirectional"))
      (node (ref "U1") (pin "28") (pinfunction "PD8_28") (pintype "bidirectional"))
    )
    (net (code "75") (name "SPI_SYNC") (class "Default")
      (node (ref "U$1") (pin "9") (pinfunction "__SYNC_9") (pintype "bidirectional"))
      (node (ref "U1") (pin "29") (pinfunction "PA8_29") (pintype "bidirectional"))
    )
    (net (code "76") (name "SWCLK") (class "Default")
      (node (ref "SV2") (pin "3") (pinfunction "3_3") (pintype "passive"))
      (node (ref "U1") (pin "37") (pinfunction "PA14_37") (pintype "bidirectional"))
    )
    (net (code "77") (name "SWDIO") (class "Default")
      (node (ref "SV2") (pin "2") (pinfunction "2_2") (pintype "passive"))
      (node (ref "U1") (pin "34") (pinfunction "PA13_34") (pintype "bidirectional"))
    )
    (net (code "78") (name "USB_DM") (class "Default")
      (node (ref "R29") (pin "2") (pinfunction "2_2") (pintype "passive"))
      (node (ref "U1") (pin "32") (pinfunction "PA11_32") (pintype "bidirectional"))
    )
    (net (code "79") (name "USB_DP") (class "Default")
      (node (ref "R28") (pin "2") (pinfunction "2_2") (pintype "passive"))
      (node (ref "R30") (pin "1") (pinfunction "1_1") (pintype "passive"))
      (node (ref "U1") (pin "33") (pinfunction "PA12_33") (pintype "bidirectional"))
    )
    (net (code "80") (name "VCCIO") (class "Default")
      (node (ref "C15") (pin "1") (pinfunction "1_1") (pintype "passive"))
      (node (ref "C16") (pin "1") (pinfunction "1_1") (pintype "passive"))
      (node (ref "C17") (pin "1") (pinfunction "1_1") (pintype "passive"))
      (node (ref "C18") (pin "1") (pinfunction "1_1") (pintype "passive"))
      (node (ref "C25") (pin "1") (pinfunction "1_1") (pintype "passive"))
      (node (ref "C3") (pin "1") (pinfunction "1_1") (pintype "passive"))
      (node (ref "R17") (pin "2") (pinfunction "2_2") (pintype "passive"))
      (node (ref "R30") (pin "2") (pinfunction "2_2") (pintype "passive"))
      (node (ref "R32") (pin "2") (pinfunction "2_2") (pintype "passive"))
      (node (ref "R33") (pin "1") (pinfunction "1_1") (pintype "passive"))
      (node (ref "U$1") (pin "12") (pinfunction "DVDD_12") (pintype "bidirectional"))
      (node (ref "U$1") (pin "13") (pinfunction "__RST_13") (pintype "bidirectional"))
      (node (ref "U$2") (pin "1") (pinfunction "VOUT_1") (pintype "bidirectional"))
      (node (ref "U$4") (pin "8") (pinfunction "VCC_8") (pintype "passive"))
      (node (ref "U1") (pin "1") (pinfunction "VBAT_1") (pintype "bidirectional"))
      (node (ref "U1") (pin "17") (pinfunction "VDD2_17") (pintype "bidirectional"))
      (node (ref "U1") (pin "24") (pinfunction "VDDSD_24") (pintype "bidirectional"))
      (node (ref "U1") (pin "25") (pinfunction "VDDREF_25") (pintype "bidirectional"))
      (node (ref "U1") (pin "48") (pinfunction "VDD1_48") (pintype "bidirectional"))
      (node (ref "U1") (pin "9") (pinfunction "VDDA_9") (pintype "bidirectional"))
    )
    (net (code "81") (name "unconnected-(J1-VBUS-Pad1)") (class "Default")
      (node (ref "J1") (pin "1") (pinfunction "VBUS_1") (pintype "bidirectional"))
    )
    (net (code "82") (name "unconnected-(JCK1-SWITCH-PadP$2_SWITCH)") (class "Default")
      (node (ref "JCK1") (pin "P$2_SWITCH") (pinfunction "SWITCH_P$2_SWITCH") (pintype "passive"))
    )
    (net (code "83") (name "unconnected-(JCK2-SWITCH-PadP$2_SWITCH)") (class "Default")
      (node (ref "JCK2") (pin "P$2_SWITCH") (pinfunction "SWITCH_P$2_SWITCH") (pintype "passive"))
    )
    (net (code "84") (name "unconnected-(JCK3-SWITCH-PadP$2_SWITCH)") (class "Default")
      (node (ref "JCK3") (pin "P$2_SWITCH") (pinfunction "SWITCH_P$2_SWITCH") (pintype "passive"))
    )
    (net (code "85") (name "unconnected-(JCK4-SWITCH-PadP$2_SWITCH)") (class "Default")
      (node (ref "JCK4") (pin "P$2_SWITCH") (pinfunction "SWITCH_P$2_SWITCH") (pintype "passive"))
    )
    (net (code "86") (name "unconnected-(JCK5-SWITCH-PadP$2_SWITCH)") (class "Default")
      (node (ref "JCK5") (pin "P$2_SWITCH") (pinfunction "SWITCH_P$2_SWITCH") (pintype "passive"))
    )
    (net (code "87") (name "unconnected-(JCK6-SWITCH-PadP$2_SWITCH)") (class "Default")
      (node (ref "JCK6") (pin "P$2_SWITCH") (pinfunction "SWITCH_P$2_SWITCH") (pintype "passive"))
    )
    (net (code "88") (name "unconnected-(JCK7-SWITCH-PadP$2_SWITCH)") (class "Default")
      (node (ref "JCK7") (pin "P$2_SWITCH") (pinfunction "SWITCH_P$2_SWITCH") (pintype "passive"))
    )
    (net (code "89") (name "unconnected-(JCK8-SWITCH-PadP$2_SWITCH)") (class "Default")
      (node (ref "JCK8") (pin "P$2_SWITCH") (pinfunction "SWITCH_P$2_SWITCH") (pintype "passive"))
    )
    (net (code "90") (name "unconnected-(MIDI_IN-SLEEVE-PadP$3_SLEEVE)") (class "Default")
      (node (ref "MIDI_IN") (pin "P$3_SLEEVE") (pinfunction "SLEEVE_P$3_SLEEVE") (pintype "passive"))
    )
    (net (code "91") (name "unconnected-(U$4-VE-Pad7)") (class "Default")
      (node (ref "U$4") (pin "7") (pinfunction "VE_7") (pintype "passive"))
    )
    (net (code "92") (name "unconnected-(U1-PA0-Pad10)") (class "Default")
      (node (ref "U1") (pin "10") (pinfunction "PA0_10") (pintype "bidirectional"))
    )
    (net (code "93") (name "unconnected-(U1-PA9-Pad30)") (class "Default")
      (node (ref "U1") (pin "30") (pinfunction "PA9_30") (pintype "bidirectional"))
    )
    (net (code "94") (name "unconnected-(U1-PA10-Pad31)") (class "Default")
      (node (ref "U1") (pin "31") (pinfunction "PA10_31") (pintype "bidirectional"))
    )
    (net (code "95") (name "unconnected-(U1-PA15-Pad38)") (class "Default")
      (node (ref "U1") (pin "38") (pinfunction "PA15_38") (pintype "bidirectional"))
    )
    (net (code "96") (name "unconnected-(U1-PB2-Pad20)") (class "Default")
      (node (ref "U1") (pin "20") (pinfunction "PB2_20") (pintype "bidirectional"))
    )
    (net (code "97") (name "unconnected-(U1-PB5-Pad41)") (class "Default")
      (node (ref "U1") (pin "41") (pinfunction "PB5_41") (pintype "bidirectional"))
    )
    (net (code "98") (name "unconnected-(U1-PC13-Pad2)") (class "Default")
      (node (ref "U1") (pin "2") (pinfunction "PC13_2") (pintype "bidirectional"))
    )
    (net (code "99") (name "unconnected-(U1-PC14-Pad3)") (class "Default")
      (node (ref "U1") (pin "3") (pinfunction "PC14_3") (pintype "bidirectional"))
    )
    (net (code "100") (name "unconnected-(U1-PC15-Pad4)") (class "Default")
      (node (ref "U1") (pin "4") (pinfunction "PC15_4") (pintype "bidirectional"))
    )
    (net (code "101") (name "unconnected-(U1-PE8-Pad21)") (class "Default")
      (node (ref "U1") (pin "21") (pinfunction "PE8_21") (pintype "bidirectional"))
    )
    (net (code "102") (name "unconnected-(U1-PE9-Pad22)") (class "Default")
      (node (ref "U1") (pin "22") (pinfunction "PE9_22") (pintype "bidirectional"))
    )
    (net (code "103") (name "unconnected-(U1-PF6-Pad35)") (class "Default")
      (node (ref "U1") (pin "35") (pinfunction "PF6_35") (pintype "bidirectional"))
    )
    (net (code "104") (name "unconnected-(U1-PF7-Pad36)") (class "Default")
      (node (ref "U1") (pin "36") (pinfunction "PF7_36") (pintype "bidirectional"))
    )
  )
)
